# POWER.net
KiCad netlist of a schematic drawn in Altium Designer
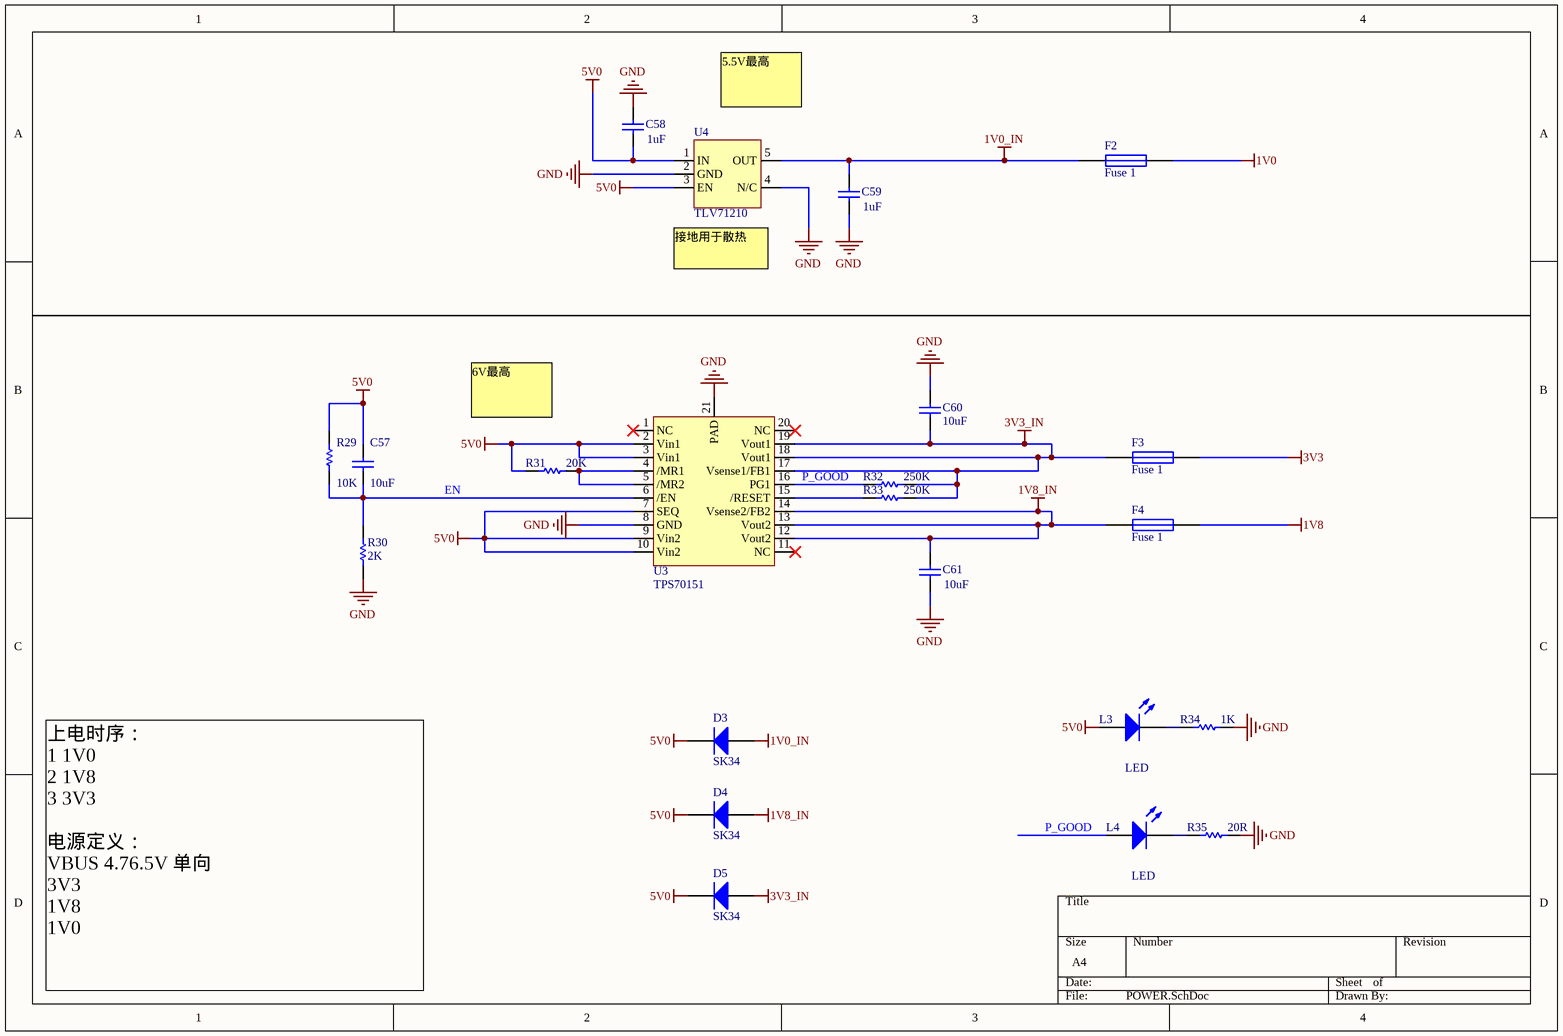
[diagram p0: POWER.SchDoc]

(export (version "E")
  (design (tool "Eeschema 10.0.6"))
  (components
    (comp (ref "C57")
      (value "10uF")
      (footprint "1608[0603]")
      (description "贴片电容")
      (fields (field (name "Comment") "Cap") (field (name "PUBLISHER") "Altium Limited"))
      (libsource (lib "Sparks") (part "Cap"))
    )
    (comp (ref "C58")
      (value "1uF")
      (footprint "1608[0603]")
      (description "贴片电容")
      (fields (field (name "Comment") "Cap") (field (name "PUBLISHER") "Altium Limited"))
      (libsource (lib "Sparks") (part "Cap"))
    )
    (comp (ref "C59")
      (value "1uF")
      (footprint "1608[0603]")
      (description "贴片电容")
      (fields (field (name "Comment") "Cap") (field (name "PUBLISHER") "Altium Limited"))
      (libsource (lib "Sparks") (part "Cap"))
    )
    (comp (ref "C60")
      (value "10uF")
      (footprint "1608[0603]")
      (description "贴片电容")
      (fields (field (name "Comment") "Cap") (field (name "PUBLISHER") "Altium Limited"))
      (libsource (lib "Sparks") (part "Cap"))
    )
    (comp (ref "C61")
      (value "10uF")
      (footprint "1608[0603]")
      (description "贴片电容")
      (fields (field (name "Comment") "Cap") (field (name "PUBLISHER") "Altium Limited"))
      (libsource (lib "Sparks") (part "Cap"))
    )
    (comp (ref "D3")
      (value "SK34")
      (footprint "1206")
      (description "High Conductance Fast Diode")
      (fields (field (name "PUBLISHER") "Altium Limited"))
      (libsource (lib "K60-V4.0") (part "Diode 1N4148"))
    )
    (comp (ref "D4")
      (value "SK34")
      (footprint "1206")
      (description "High Conductance Fast Diode")
      (fields (field (name "PUBLISHER") "Altium Limited"))
      (libsource (lib "K60-V4.0") (part "Diode 1N4148"))
    )
    (comp (ref "D5")
      (value "SK34")
      (footprint "1206")
      (description "High Conductance Fast Diode")
      (fields (field (name "PUBLISHER") "Altium Limited"))
      (libsource (lib "K60-V4.0") (part "Diode 1N4148"))
    )
    (comp (ref "F2")
      (value "Fuse 1")
      (footprint "1206")
      (description "Fuse")
      (fields (field (name "PUBLISHER") "Altium Limited"))
      (libsource (lib "Miscellaneous Devices") (part "Fuse 1"))
    )
    (comp (ref "F3")
      (value "Fuse 1")
      (footprint "1206")
      (description "Fuse")
      (fields (field (name "PUBLISHER") "Altium Limited"))
      (libsource (lib "Miscellaneous Devices") (part "Fuse 1"))
    )
    (comp (ref "F4")
      (value "Fuse 1")
      (footprint "1206")
      (description "Fuse")
      (fields (field (name "PUBLISHER") "Altium Limited"))
      (libsource (lib "Miscellaneous Devices") (part "Fuse 1"))
    )
    (comp (ref "L3") (value "LED") (footprint "1608[0603]") (libsource (lib "Sparks") (part "LED")))
    (comp (ref "L4") (value "LED") (footprint "1608[0603]") (libsource (lib "Sparks") (part "LED")))
    (comp (ref "R29")
      (value "10K")
      (footprint "1608[0603]")
      (description "贴片电阻")
      (fields (field (name "Comment") "Res") (field (name "PUBLISHER") "Altium Limited"))
      (libsource (lib "Sparks") (part "Res"))
    )
    (comp (ref "R30")
      (value "2K")
      (footprint "1608[0603]")
      (description "贴片电阻")
      (fields (field (name "Comment") "Res") (field (name "PUBLISHER") "Altium Limited"))
      (libsource (lib "Sparks") (part "Res"))
    )
    (comp (ref "R31")
      (value "20K")
      (footprint "1608[0603]")
      (description "贴片电阻")
      (fields (field (name "Comment") "Res") (field (name "PUBLISHER") "Altium Limited"))
      (libsource (lib "Sparks") (part "Res"))
    )
    (comp (ref "R32")
      (value "250K")
      (footprint "1608[0603]")
      (description "贴片电阻")
      (fields (field (name "Comment") "Res") (field (name "PUBLISHER") "Altium Limited"))
      (libsource (lib "Sparks") (part "Res"))
    )
    (comp (ref "R33")
      (value "250K")
      (footprint "1608[0603]")
      (description "贴片电阻")
      (fields (field (name "Comment") "Res") (field (name "PUBLISHER") "Altium Limited"))
      (libsource (lib "Sparks") (part "Res"))
    )
    (comp (ref "R34")
      (value "1K")
      (footprint "1608[0603]")
      (description "贴片电阻")
      (fields (field (name "Comment") "Res") (field (name "PUBLISHER") "Altium Limited"))
      (libsource (lib "Sparks") (part "Res"))
    )
    (comp (ref "R35")
      (value "20R")
      (footprint "1608[0603]")
      (description "贴片电阻")
      (fields (field (name "Comment") "Res") (field (name "PUBLISHER") "Altium Limited"))
      (libsource (lib "Sparks") (part "Res"))
    )
    (comp (ref "U3") (value "TPS70151") (footprint "TPS701") (libsource (lib "Schlib1") (part "TPS701")))
    (comp (ref "U4") (value "TLV71210") (footprint "TLV712") (libsource (lib "Schlib1") (part "TLV712")))
  )
  (nets
    (net (code "1") (name "/EN") (class "Default")
      (node (ref "C57") (pin "2") (pinfunction "2_2") (pintype "passive"))
      (node (ref "R29") (pin "2") (pinfunction "2_2") (pintype "passive"))
      (node (ref "R30") (pin "1") (pinfunction "1_1") (pintype "passive"))
      (node (ref "U3") (pin "6") (pinfunction "/EN_6") (pintype "passive"))
    )
    (net (code "2") (name "/P_GOOD") (class "Default")
      (node (ref "L4") (pin "1") (pinfunction "A_1") (pintype "passive"))
      (node (ref "R32") (pin "2") (pinfunction "2_2") (pintype "passive"))
      (node (ref "U3") (pin "16") (pinfunction "PG1_16") (pintype "passive"))
    )
    (net (code "3") (name "1V0") (class "Default")
      (node (ref "F2") (pin "1") (pinfunction "1_1") (pintype "passive"))
    )
    (net (code "4") (name "1V0_IN") (class "Default")
      (node (ref "C59") (pin "1") (pinfunction "1_1") (pintype "passive"))
      (node (ref "D3") (pin "1") (pinfunction "A_1") (pintype "passive"))
      (node (ref "F2") (pin "2") (pinfunction "2_2") (pintype "passive"))
      (node (ref "U4") (pin "5") (pinfunction "OUT_5") (pintype "passive"))
    )
    (net (code "5") (name "1V8") (class "Default")
      (node (ref "F4") (pin "1") (pinfunction "1_1") (pintype "passive"))
    )
    (net (code "6") (name "1V8_IN") (class "Default")
      (node (ref "C61") (pin "1") (pinfunction "1_1") (pintype "passive"))
      (node (ref "D4") (pin "1") (pinfunction "A_1") (pintype "passive"))
      (node (ref "F4") (pin "2") (pinfunction "2_2") (pintype "passive"))
      (node (ref "U3") (pin "12") (pinfunction "Vout2_12") (pintype "passive"))
      (node (ref "U3") (pin "13") (pinfunction "Vout2_13") (pintype "passive"))
      (node (ref "U3") (pin "14") (pinfunction "Vsense2/FB2_14") (pintype "passive"))
    )
    (net (code "7") (name "3V3") (class "Default")
      (node (ref "F3") (pin "1") (pinfunction "1_1") (pintype "passive"))
    )
    (net (code "8") (name "3V3_IN") (class "Default")
      (node (ref "C60") (pin "1") (pinfunction "1_1") (pintype "passive"))
      (node (ref "D5") (pin "1") (pinfunction "A_1") (pintype "passive"))
      (node (ref "F3") (pin "2") (pinfunction "2_2") (pintype "passive"))
      (node (ref "R32") (pin "1") (pinfunction "1_1") (pintype "passive"))
      (node (ref "R33") (pin "1") (pinfunction "1_1") (pintype "passive"))
      (node (ref "U3") (pin "17") (pinfunction "Vsense1/FB1_17") (pintype "passive"))
      (node (ref "U3") (pin "18") (pinfunction "Vout1_18") (pintype "passive"))
      (node (ref "U3") (pin "19") (pinfunction "Vout1_19") (pintype "passive"))
    )
    (net (code "9") (name "5V0") (class "Default")
      (node (ref "C57") (pin "1") (pinfunction "1_1") (pintype "passive"))
      (node (ref "C58") (pin "2") (pinfunction "2_2") (pintype "passive"))
      (node (ref "D3") (pin "2") (pinfunction "K_2") (pintype "passive"))
      (node (ref "D4") (pin "2") (pinfunction "K_2") (pintype "passive"))
      (node (ref "D5") (pin "2") (pinfunction "K_2") (pintype "passive"))
      (node (ref "L3") (pin "1") (pinfunction "A_1") (pintype "passive"))
      (node (ref "R29") (pin "1") (pinfunction "1_1") (pintype "passive"))
      (node (ref "R31") (pin "2") (pinfunction "2_2") (pintype "passive"))
      (node (ref "U3") (pin "10") (pinfunction "Vin2_10") (pintype "passive"))
      (node (ref "U3") (pin "2") (pinfunction "Vin1_2") (pintype "passive"))
      (node (ref "U3") (pin "3") (pinfunction "Vin1_3") (pintype "passive"))
      (node (ref "U3") (pin "7") (pinfunction "SEQ_7") (pintype "passive"))
      (node (ref "U3") (pin "9") (pinfunction "Vin2_9") (pintype "passive"))
      (node (ref "U4") (pin "1") (pinfunction "IN_1") (pintype "passive"))
      (node (ref "U4") (pin "3") (pinfunction "EN_3") (pintype "passive"))
    )
    (net (code "10") (name "GND") (class "Default")
      (node (ref "C58") (pin "1") (pinfunction "1_1") (pintype "passive"))
      (node (ref "C59") (pin "2") (pinfunction "2_2") (pintype "passive"))
      (node (ref "C60") (pin "2") (pinfunction "2_2") (pintype "passive"))
      (node (ref "C61") (pin "2") (pinfunction "2_2") (pintype "passive"))
      (node (ref "R30") (pin "2") (pinfunction "2_2") (pintype "passive"))
      (node (ref "R34") (pin "1") (pinfunction "1_1") (pintype "passive"))
      (node (ref "R35") (pin "1") (pinfunction "1_1") (pintype "passive"))
      (node (ref "U3") (pin "21") (pinfunction "PAD_21") (pintype "passive"))
      (node (ref "U3") (pin "8") (pinfunction "GND_8") (pintype "passive"))
      (node (ref "U4") (pin "2") (pinfunction "GND_2") (pintype "passive"))
      (node (ref "U4") (pin "4") (pinfunction "N/C_4") (pintype "passive"))
    )
    (net (code "11") (name "Net-(L3-K)") (class "Default")
      (node (ref "L3") (pin "2") (pinfunction "K_2") (pintype "passive"))
      (node (ref "R34") (pin "2") (pinfunction "2_2") (pintype "passive"))
    )
    (net (code "12") (name "Net-(L4-K)") (class "Default")
      (node (ref "L4") (pin "2") (pinfunction "K_2") (pintype "passive"))
      (node (ref "R35") (pin "2") (pinfunction "2_2") (pintype "passive"))
    )
    (net (code "13") (name "Net-(U3-{slash}MR1)") (class "Default")
      (node (ref "R31") (pin "1") (pinfunction "1_1") (pintype "passive"))
      (node (ref "U3") (pin "4") (pinfunction "/MR1_4") (pintype "passive"))
      (node (ref "U3") (pin "5") (pinfunction "/MR2_5") (pintype "passive"))
    )
    (net (code "14") (name "Net-(U3-{slash}RESET)") (class "Default")
      (node (ref "R33") (pin "2") (pinfunction "2_2") (pintype "passive"))
      (node (ref "U3") (pin "15") (pinfunction "/RESET_15") (pintype "passive"))
    )
    (net (code "15") (name "unconnected-(U3-NC-Pad1)") (class "Default")
      (node (ref "U3") (pin "1") (pinfunction "NC_1") (pintype "passive+no_connect"))
    )
    (net (code "16") (name "unconnected-(U3-NC-Pad11)") (class "Default")
      (node (ref "U3") (pin "11") (pinfunction "NC_11") (pintype "passive+no_connect"))
    )
    (net (code "17") (name "unconnected-(U3-NC-Pad20)") (class "Default")
      (node (ref "U3") (pin "20") (pinfunction "NC_20") (pintype "passive+no_connect"))
    )
  )
)
